# SCB_S1000.net
KiCad netlist of a schematic drawn in EAGLE
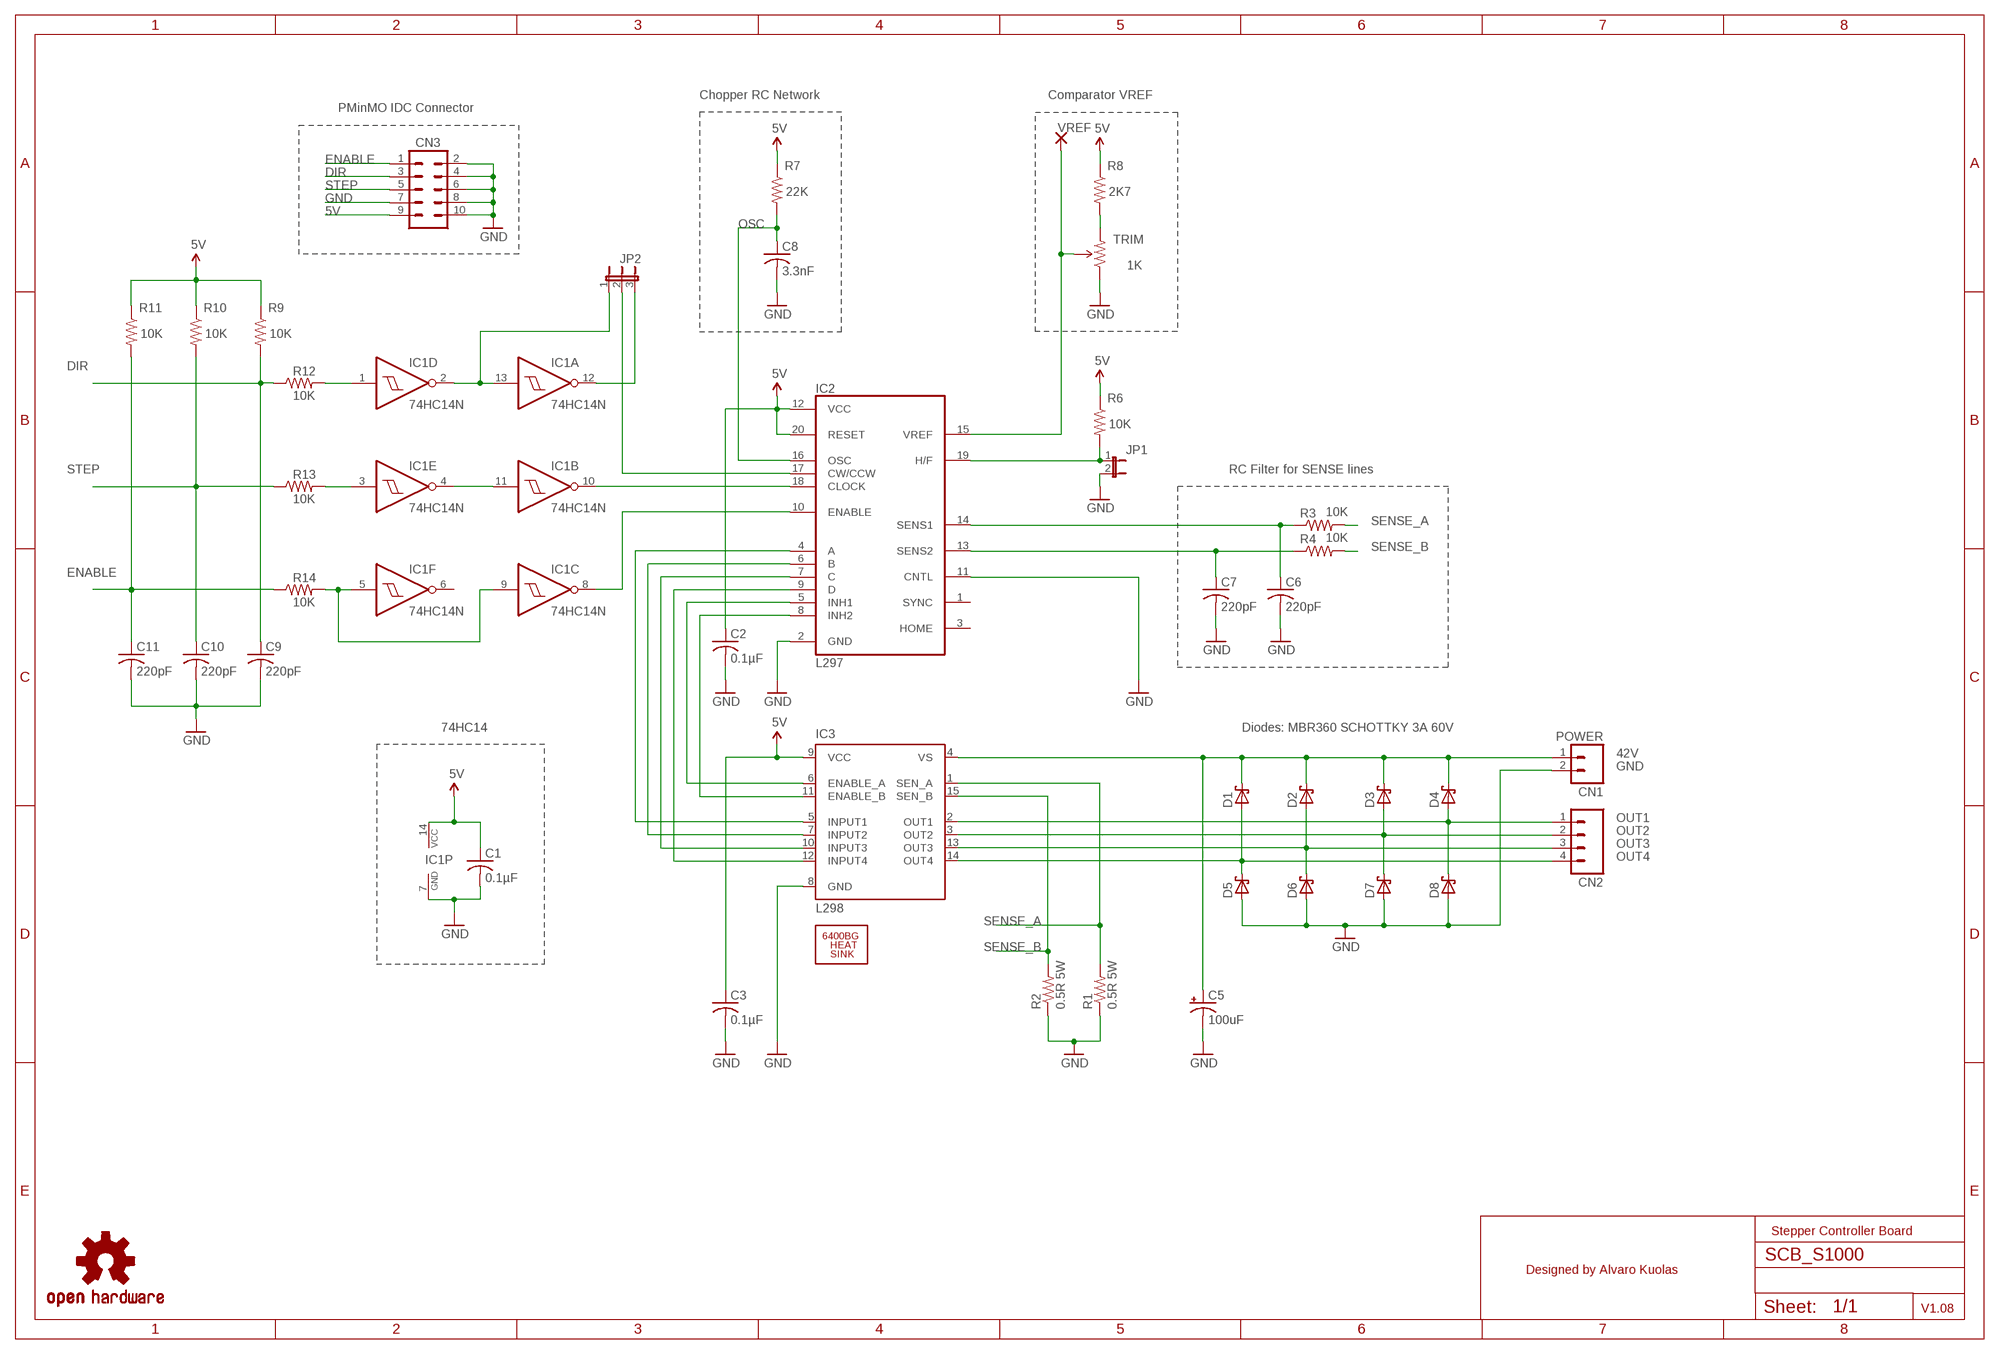
[diagram p0: schematic, sheet 1]

(export (version "E")
  (design (tool "Eeschema 10.0.6"))
  (components
    (comp (ref "C1")
      (value "0.1µF")
      (footprint "eagle-import:C050-024X044")
      (libsource (lib "eagle-import") (part "C-US050-024X044"))
    )
    (comp (ref "C2")
      (value "0.1µF")
      (footprint "eagle-import:C050-024X044")
      (libsource (lib "eagle-import") (part "C-US050-024X044"))
    )
    (comp (ref "C3")
      (value "0.1µF")
      (footprint "eagle-import:C050-024X044")
      (libsource (lib "eagle-import") (part "C-US050-024X044"))
    )
    (comp (ref "C5")
      (value "100uF")
      (footprint "eagle-import:E5-10,5")
      (libsource (lib "eagle-import") (part "CPOL-USE5-10.5"))
    )
    (comp (ref "C6")
      (value "220pF")
      (footprint "eagle-import:C050-024X044")
      (libsource (lib "eagle-import") (part "C-US050-024X044"))
    )
    (comp (ref "C7")
      (value "220pF")
      (footprint "eagle-import:C050-024X044")
      (libsource (lib "eagle-import") (part "C-US050-024X044"))
    )
    (comp (ref "C8")
      (value "3.3nF")
      (footprint "eagle-import:C050-024X044")
      (libsource (lib "eagle-import") (part "C-US050-024X044"))
    )
    (comp (ref "C9")
      (value "220pF")
      (footprint "eagle-import:C050-024X044")
      (libsource (lib "eagle-import") (part "C-US050-024X044"))
    )
    (comp (ref "C10")
      (value "220pF")
      (footprint "eagle-import:C050-024X044")
      (libsource (lib "eagle-import") (part "C-US050-024X044"))
    )
    (comp (ref "C11")
      (value "220pF")
      (footprint "eagle-import:C050-024X044")
      (libsource (lib "eagle-import") (part "C-US050-024X044"))
    )
    (comp (ref "CN1")
      (value "POWER")
      (footprint "eagle-import:SCREWTERMINAL-3.5MM-2")
      (libsource (lib "eagle-import") (part "M023.5MM"))
    )
    (comp (ref "CN2")
      (value "STEPPER")
      (footprint "eagle-import:SCREWTERMINAL-3.5MM-4")
      (libsource (lib "eagle-import") (part "M04SCREW"))
    )
    (comp (ref "CN3")
      (value "M05X2SHD")
      (footprint "eagle-import:2X5-SHROUDED")
      (libsource (lib "eagle-import") (part "M05X2SHD"))
    )
    (comp (ref "D1")
      (value "MBR360")
      (footprint "eagle-import:DO201T15")
      (libsource (lib "eagle-import") (part "SCHOTTKY-DIODEDO201T15"))
    )
    (comp (ref "D2")
      (value "MBR360")
      (footprint "eagle-import:DO201T15")
      (libsource (lib "eagle-import") (part "SCHOTTKY-DIODEDO201T15"))
    )
    (comp (ref "D3")
      (value "MBR360")
      (footprint "eagle-import:DO201T15")
      (libsource (lib "eagle-import") (part "SCHOTTKY-DIODEDO201T15"))
    )
    (comp (ref "D4")
      (value "MBR360")
      (footprint "eagle-import:DO201T15")
      (libsource (lib "eagle-import") (part "SCHOTTKY-DIODEDO201T15"))
    )
    (comp (ref "D5")
      (value "MBR360")
      (footprint "eagle-import:DO201T15")
      (libsource (lib "eagle-import") (part "SCHOTTKY-DIODEDO201T15"))
    )
    (comp (ref "D6")
      (value "MBR360")
      (footprint "eagle-import:DO201T15")
      (libsource (lib "eagle-import") (part "SCHOTTKY-DIODEDO201T15"))
    )
    (comp (ref "D7")
      (value "MBR360")
      (footprint "eagle-import:DO201T15")
      (libsource (lib "eagle-import") (part "SCHOTTKY-DIODEDO201T15"))
    )
    (comp (ref "D8")
      (value "MBR360")
      (footprint "eagle-import:DO201T15")
      (libsource (lib "eagle-import") (part "SCHOTTKY-DIODEDO201T15"))
    )
    (comp (ref "IC1")
      (value "74HC14N")
      (footprint "eagle-import:DIL14")
      (libsource (lib "eagle-import") (part "7414NHC"))
    )
    (comp (ref "IC2")
      (value "L297")
      (footprint "eagle-import:DIL20")
      (libsource (lib "eagle-import") (part "L297"))
    )
    (comp (ref "IC3")
      (value "L298")
      (footprint "eagle-import:MULTIWATT-15")
      (libsource (lib "eagle-import") (part "L298"))
    )
    (comp (ref "JP1")
      (value "H/F")
      (footprint "eagle-import:1X02")
      (libsource (lib "eagle-import") (part "JUMPER-2PTH"))
    )
    (comp (ref "JP2")
      (value "DIR")
      (footprint "eagle-import:1X03")
      (libsource (lib "eagle-import") (part "JUMPER-3PTH"))
    )
    (comp (ref "R1")
      (value "0.5R 5W")
      (footprint "eagle-import:0922_22")
      (libsource (lib "eagle-import") (part "R-US_0922/22"))
    )
    (comp (ref "R2")
      (value "0.5R 5W")
      (footprint "eagle-import:0922_22")
      (libsource (lib "eagle-import") (part "R-US_0922/22"))
    )
    (comp (ref "R3")
      (value "10K")
      (footprint "eagle-import:0204_5")
      (libsource (lib "eagle-import") (part "R-US_0204/5"))
    )
    (comp (ref "R4")
      (value "10K")
      (footprint "eagle-import:0204_5")
      (libsource (lib "eagle-import") (part "R-US_0204/5"))
    )
    (comp (ref "R6")
      (value "10K")
      (footprint "eagle-import:0204_5")
      (libsource (lib "eagle-import") (part "R-US_0204/5"))
    )
    (comp (ref "R7")
      (value "22K")
      (footprint "eagle-import:0204_5")
      (libsource (lib "eagle-import") (part "R-US_0204/5"))
    )
    (comp (ref "R8")
      (value "2K7")
      (footprint "eagle-import:0204_5")
      (libsource (lib "eagle-import") (part "R-US_0204/5"))
    )
    (comp (ref "R9")
      (value "10K")
      (footprint "eagle-import:0204_5")
      (libsource (lib "eagle-import") (part "R-US_0204/5"))
    )
    (comp (ref "R10")
      (value "10K")
      (footprint "eagle-import:0204_5")
      (libsource (lib "eagle-import") (part "R-US_0204/5"))
    )
    (comp (ref "R11")
      (value "10K")
      (footprint "eagle-import:0204_5")
      (libsource (lib "eagle-import") (part "R-US_0204/5"))
    )
    (comp (ref "R12")
      (value "10K")
      (footprint "eagle-import:0204_5")
      (libsource (lib "eagle-import") (part "R-US_0204/5"))
    )
    (comp (ref "R13")
      (value "10K")
      (footprint "eagle-import:0204_5")
      (libsource (lib "eagle-import") (part "R-US_0204/5"))
    )
    (comp (ref "R14")
      (value "10K")
      (footprint "eagle-import:0204_5")
      (libsource (lib "eagle-import") (part "R-US_0204/5"))
    )
    (comp (ref "TRIM")
      (value "1K")
      (footprint "eagle-import:3362U-2")
      (libsource (lib "eagle-import") (part "TRIMPOT"))
    )
    (comp (ref "U$2")
      (value "6400BG_HEATSINK")
      (footprint "eagle-import:6400BG_HEATSINK")
      (libsource (lib "eagle-import") (part "6400BG_HEATSINK"))
    )
    (comp (ref "U$9")
      (value "OSHW-LOGOL")
      (footprint "eagle-import:OSHW-LOGO-L")
      (libsource (lib "eagle-import") (part "OSHW-LOGOL"))
    )
    (comp (ref "VREF")
      (value "VREF")
      (footprint "eagle-import:1,6_0,9")
      (libsource (lib "eagle-import") (part "1,6/0,9"))
    )
  )
  (nets
    (net (code "1") (name "/42V") (class "Default")
      (node (ref "C5") (pin "+") (pinfunction "+_+") (pintype "passive"))
      (node (ref "CN1") (pin "1") (pinfunction "1_1") (pintype "passive"))
      (node (ref "D1") (pin "C") (pinfunction "C_C") (pintype "passive"))
      (node (ref "D2") (pin "C") (pinfunction "C_C") (pintype "passive"))
      (node (ref "D3") (pin "C") (pinfunction "C_C") (pintype "passive"))
      (node (ref "D4") (pin "C") (pinfunction "C_C") (pintype "passive"))
      (node (ref "IC3") (pin "4") (pinfunction "VS_4") (pintype "power_in"))
    )
    (net (code "2") (name "/DIR") (class "Default")
      (node (ref "C9") (pin "1") (pinfunction "1_1") (pintype "passive"))
      (node (ref "CN3") (pin "3") (pinfunction "3_3") (pintype "passive"))
      (node (ref "R12") (pin "1") (pinfunction "1_1") (pintype "passive"))
      (node (ref "R9") (pin "2") (pinfunction "2_2") (pintype "passive"))
    )
    (net (code "3") (name "/ENABLE") (class "Default")
      (node (ref "C11") (pin "1") (pinfunction "1_1") (pintype "passive"))
      (node (ref "CN3") (pin "1") (pinfunction "1_1") (pintype "passive"))
      (node (ref "R11") (pin "2") (pinfunction "2_2") (pintype "passive"))
      (node (ref "R14") (pin "1") (pinfunction "1_1") (pintype "passive"))
    )
    (net (code "4") (name "/OSC") (class "Default")
      (node (ref "C8") (pin "1") (pinfunction "1_1") (pintype "passive"))
      (node (ref "IC2") (pin "16") (pinfunction "OSC_16") (pintype "bidirectional"))
      (node (ref "R7") (pin "2") (pinfunction "2_2") (pintype "passive"))
    )
    (net (code "5") (name "/OUT1") (class "Default")
      (node (ref "CN2") (pin "1") (pinfunction "1_1") (pintype "passive"))
      (node (ref "D4") (pin "A") (pinfunction "A_A") (pintype "passive"))
      (node (ref "D8") (pin "C") (pinfunction "C_C") (pintype "passive"))
      (node (ref "IC3") (pin "2") (pinfunction "OUT1_2") (pintype "output"))
    )
    (net (code "6") (name "/OUT2") (class "Default")
      (node (ref "CN2") (pin "2") (pinfunction "2_2") (pintype "passive"))
      (node (ref "D3") (pin "A") (pinfunction "A_A") (pintype "passive"))
      (node (ref "D7") (pin "C") (pinfunction "C_C") (pintype "passive"))
      (node (ref "IC3") (pin "3") (pinfunction "OUT2_3") (pintype "output"))
    )
    (net (code "7") (name "/OUT3") (class "Default")
      (node (ref "CN2") (pin "3") (pinfunction "3_3") (pintype "passive"))
      (node (ref "D2") (pin "A") (pinfunction "A_A") (pintype "passive"))
      (node (ref "D6") (pin "C") (pinfunction "C_C") (pintype "passive"))
      (node (ref "IC3") (pin "13") (pinfunction "OUT3_13") (pintype "output"))
    )
    (net (code "8") (name "/OUT4") (class "Default")
      (node (ref "CN2") (pin "4") (pinfunction "4_4") (pintype "passive"))
      (node (ref "D1") (pin "A") (pinfunction "A_A") (pintype "passive"))
      (node (ref "D5") (pin "C") (pinfunction "C_C") (pintype "passive"))
      (node (ref "IC3") (pin "14") (pinfunction "OUT4_14") (pintype "output"))
    )
    (net (code "9") (name "/SENSE_A") (class "Default")
      (node (ref "IC3") (pin "1") (pinfunction "SEN_A_1") (pintype "input"))
      (node (ref "R1") (pin "2") (pinfunction "2_2") (pintype "passive"))
      (node (ref "R3") (pin "2") (pinfunction "2_2") (pintype "passive"))
    )
    (net (code "10") (name "/SENSE_B") (class "Default")
      (node (ref "IC3") (pin "15") (pinfunction "SEN_B_15") (pintype "input"))
      (node (ref "R2") (pin "2") (pinfunction "2_2") (pintype "passive"))
      (node (ref "R4") (pin "2") (pinfunction "2_2") (pintype "passive"))
    )
    (net (code "11") (name "/STEP") (class "Default")
      (node (ref "C10") (pin "1") (pinfunction "1_1") (pintype "passive"))
      (node (ref "CN3") (pin "5") (pinfunction "5_5") (pintype "passive"))
      (node (ref "R10") (pin "2") (pinfunction "2_2") (pintype "passive"))
      (node (ref "R13") (pin "1") (pinfunction "1_1") (pintype "passive"))
    )
    (net (code "12") (name "5V") (class "Default")
      (node (ref "C1") (pin "1") (pinfunction "1_1") (pintype "passive"))
      (node (ref "C2") (pin "1") (pinfunction "1_1") (pintype "passive"))
      (node (ref "C3") (pin "1") (pinfunction "1_1") (pintype "passive"))
      (node (ref "CN3") (pin "9") (pinfunction "9_9") (pintype "passive"))
      (node (ref "IC1") (pin "14") (pinfunction "VCC_14") (pintype "power_in"))
      (node (ref "IC2") (pin "12") (pinfunction "VCC_12") (pintype "power_in"))
      (node (ref "IC2") (pin "20") (pinfunction "RESET_20") (pintype "input"))
      (node (ref "IC3") (pin "9") (pinfunction "VCC_9") (pintype "power_in"))
      (node (ref "R10") (pin "1") (pinfunction "1_1") (pintype "passive"))
      (node (ref "R11") (pin "1") (pinfunction "1_1") (pintype "passive"))
      (node (ref "R6") (pin "1") (pinfunction "1_1") (pintype "passive"))
      (node (ref "R7") (pin "1") (pinfunction "1_1") (pintype "passive"))
      (node (ref "R8") (pin "1") (pinfunction "1_1") (pintype "passive"))
      (node (ref "R9") (pin "1") (pinfunction "1_1") (pintype "passive"))
    )
    (net (code "13") (name "GND") (class "Default")
      (node (ref "C1") (pin "2") (pinfunction "2_2") (pintype "passive"))
      (node (ref "C10") (pin "2") (pinfunction "2_2") (pintype "passive"))
      (node (ref "C11") (pin "2") (pinfunction "2_2") (pintype "passive"))
      (node (ref "C2") (pin "2") (pinfunction "2_2") (pintype "passive"))
      (node (ref "C3") (pin "2") (pinfunction "2_2") (pintype "passive"))
      (node (ref "C5") (pin "-") (pinfunction "-_-") (pintype "passive"))
      (node (ref "C6") (pin "2") (pinfunction "2_2") (pintype "passive"))
      (node (ref "C7") (pin "2") (pinfunction "2_2") (pintype "passive"))
      (node (ref "C8") (pin "2") (pinfunction "2_2") (pintype "passive"))
      (node (ref "C9") (pin "2") (pinfunction "2_2") (pintype "passive"))
      (node (ref "CN1") (pin "2") (pinfunction "2_2") (pintype "passive"))
      (node (ref "CN3") (pin "10") (pinfunction "10_10") (pintype "passive"))
      (node (ref "CN3") (pin "2") (pinfunction "2_2") (pintype "passive"))
      (node (ref "CN3") (pin "4") (pinfunction "4_4") (pintype "passive"))
      (node (ref "CN3") (pin "6") (pinfunction "6_6") (pintype "passive"))
      (node (ref "CN3") (pin "7") (pinfunction "7_7") (pintype "passive"))
      (node (ref "CN3") (pin "8") (pinfunction "8_8") (pintype "passive"))
      (node (ref "D5") (pin "A") (pinfunction "A_A") (pintype "passive"))
      (node (ref "D6") (pin "A") (pinfunction "A_A") (pintype "passive"))
      (node (ref "D7") (pin "A") (pinfunction "A_A") (pintype "passive"))
      (node (ref "D8") (pin "A") (pinfunction "A_A") (pintype "passive"))
      (node (ref "IC1") (pin "7") (pinfunction "GND_7") (pintype "power_in"))
      (node (ref "IC2") (pin "11") (pinfunction "CNTL_11") (pintype "input"))
      (node (ref "IC2") (pin "2") (pinfunction "GND_2") (pintype "power_in"))
      (node (ref "IC3") (pin "8") (pinfunction "GND_8") (pintype "power_in"))
      (node (ref "JP1") (pin "2") (pinfunction "2_2") (pintype "passive"))
      (node (ref "R1") (pin "1") (pinfunction "1_1") (pintype "passive"))
      (node (ref "R2") (pin "1") (pinfunction "1_1") (pintype "passive"))
      (node (ref "TRIM") (pin "1") (pinfunction "CCW_1") (pintype "passive"))
    )
    (net (code "14") (name "Net-(IC1A-I)") (class "Default")
      (node (ref "IC1") (pin "13") (pinfunction "I_13") (pintype "input"))
      (node (ref "IC1") (pin "2") (pinfunction "O_2") (pintype "output"))
      (node (ref "JP2") (pin "1") (pinfunction "1_1") (pintype "passive"))
    )
    (net (code "15") (name "Net-(IC1A-O)") (class "Default")
      (node (ref "IC1") (pin "12") (pinfunction "O_12") (pintype "output"))
      (node (ref "JP2") (pin "3") (pinfunction "3_3") (pintype "passive"))
    )
    (net (code "16") (name "Net-(IC1B-I)") (class "Default")
      (node (ref "IC1") (pin "11") (pinfunction "I_11") (pintype "input"))
      (node (ref "IC1") (pin "4") (pinfunction "O_4") (pintype "output"))
    )
    (net (code "17") (name "Net-(IC1B-O)") (class "Default")
      (node (ref "IC1") (pin "10") (pinfunction "O_10") (pintype "output"))
      (node (ref "IC2") (pin "18") (pinfunction "CLOCK_18") (pintype "input"))
    )
    (net (code "18") (name "Net-(IC1C-I)") (class "Default")
      (node (ref "IC1") (pin "5") (pinfunction "I_5") (pintype "input"))
      (node (ref "IC1") (pin "9") (pinfunction "I_9") (pintype "input"))
      (node (ref "R14") (pin "2") (pinfunction "2_2") (pintype "passive"))
    )
    (net (code "19") (name "Net-(IC1C-O)") (class "Default")
      (node (ref "IC1") (pin "8") (pinfunction "O_8") (pintype "output"))
      (node (ref "IC2") (pin "10") (pinfunction "ENABLE_10") (pintype "input"))
    )
    (net (code "20") (name "Net-(IC1D-I)") (class "Default")
      (node (ref "IC1") (pin "1") (pinfunction "I_1") (pintype "input"))
      (node (ref "R12") (pin "2") (pinfunction "2_2") (pintype "passive"))
    )
    (net (code "21") (name "Net-(IC1E-I)") (class "Default")
      (node (ref "IC1") (pin "3") (pinfunction "I_3") (pintype "input"))
      (node (ref "R13") (pin "2") (pinfunction "2_2") (pintype "passive"))
    )
    (net (code "22") (name "Net-(IC2-A)") (class "Default")
      (node (ref "IC2") (pin "4") (pinfunction "A_4") (pintype "output"))
      (node (ref "IC3") (pin "5") (pinfunction "INPUT1_5") (pintype "input"))
    )
    (net (code "23") (name "Net-(IC2-B)") (class "Default")
      (node (ref "IC2") (pin "6") (pinfunction "B_6") (pintype "output"))
      (node (ref "IC3") (pin "7") (pinfunction "INPUT2_7") (pintype "input"))
    )
    (net (code "24") (name "Net-(IC2-C)") (class "Default")
      (node (ref "IC2") (pin "7") (pinfunction "C_7") (pintype "output"))
      (node (ref "IC3") (pin "10") (pinfunction "INPUT3_10") (pintype "input"))
    )
    (net (code "25") (name "Net-(IC2-CW{slash}CCW)") (class "Default")
      (node (ref "IC2") (pin "17") (pinfunction "CW/CCW_17") (pintype "input"))
      (node (ref "JP2") (pin "2") (pinfunction "2_2") (pintype "passive"))
    )
    (net (code "26") (name "Net-(IC2-D)") (class "Default")
      (node (ref "IC2") (pin "9") (pinfunction "D_9") (pintype "output"))
      (node (ref "IC3") (pin "12") (pinfunction "INPUT4_12") (pintype "input"))
    )
    (net (code "27") (name "Net-(IC2-H{slash}F)") (class "Default")
      (node (ref "IC2") (pin "19") (pinfunction "H/F_19") (pintype "input"))
      (node (ref "JP1") (pin "1") (pinfunction "1_1") (pintype "passive"))
      (node (ref "R6") (pin "2") (pinfunction "2_2") (pintype "passive"))
    )
    (net (code "28") (name "Net-(IC2-INH1)") (class "Default")
      (node (ref "IC2") (pin "5") (pinfunction "INH1_5") (pintype "output"))
      (node (ref "IC3") (pin "6") (pinfunction "ENABLE_A_6") (pintype "input"))
    )
    (net (code "29") (name "Net-(IC2-INH2)") (class "Default")
      (node (ref "IC2") (pin "8") (pinfunction "INH2_8") (pintype "output"))
      (node (ref "IC3") (pin "11") (pinfunction "ENABLE_B_11") (pintype "input"))
    )
    (net (code "30") (name "Net-(IC2-SENS1)") (class "Default")
      (node (ref "C6") (pin "1") (pinfunction "1_1") (pintype "passive"))
      (node (ref "IC2") (pin "14") (pinfunction "SENS1_14") (pintype "output"))
      (node (ref "R3") (pin "1") (pinfunction "1_1") (pintype "passive"))
    )
    (net (code "31") (name "Net-(IC2-SENS2)") (class "Default")
      (node (ref "C7") (pin "1") (pinfunction "1_1") (pintype "passive"))
      (node (ref "IC2") (pin "13") (pinfunction "SENS2_13") (pintype "output"))
      (node (ref "R4") (pin "1") (pinfunction "1_1") (pintype "passive"))
    )
    (net (code "32") (name "Net-(IC2-VREF)") (class "Default")
      (node (ref "IC2") (pin "15") (pinfunction "VREF_15") (pintype "input"))
      (node (ref "TRIM") (pin "2") (pinfunction "WIPER_2") (pintype "passive"))
      (node (ref "VREF") (pin "1") (pinfunction "P_1") (pintype "passive"))
    )
    (net (code "33") (name "Net-(TRIM-CW)") (class "Default")
      (node (ref "R8") (pin "2") (pinfunction "2_2") (pintype "passive"))
      (node (ref "TRIM") (pin "3") (pinfunction "CW_3") (pintype "passive"))
    )
    (net (code "34") (name "unconnected-(IC1F-O-Pad6)") (class "Default")
      (node (ref "IC1") (pin "6") (pinfunction "O_6") (pintype "output"))
    )
    (net (code "35") (name "unconnected-(IC2-HOME-Pad3)") (class "Default")
      (node (ref "IC2") (pin "3") (pinfunction "HOME_3") (pintype "output"))
    )
    (net (code "36") (name "unconnected-(IC2-SYNC-Pad1)") (class "Default")
      (node (ref "IC2") (pin "1") (pinfunction "SYNC_1") (pintype "output"))
    )
  )
)
